# MIC.net
KiCad netlist of a schematic drawn in Altium Designer
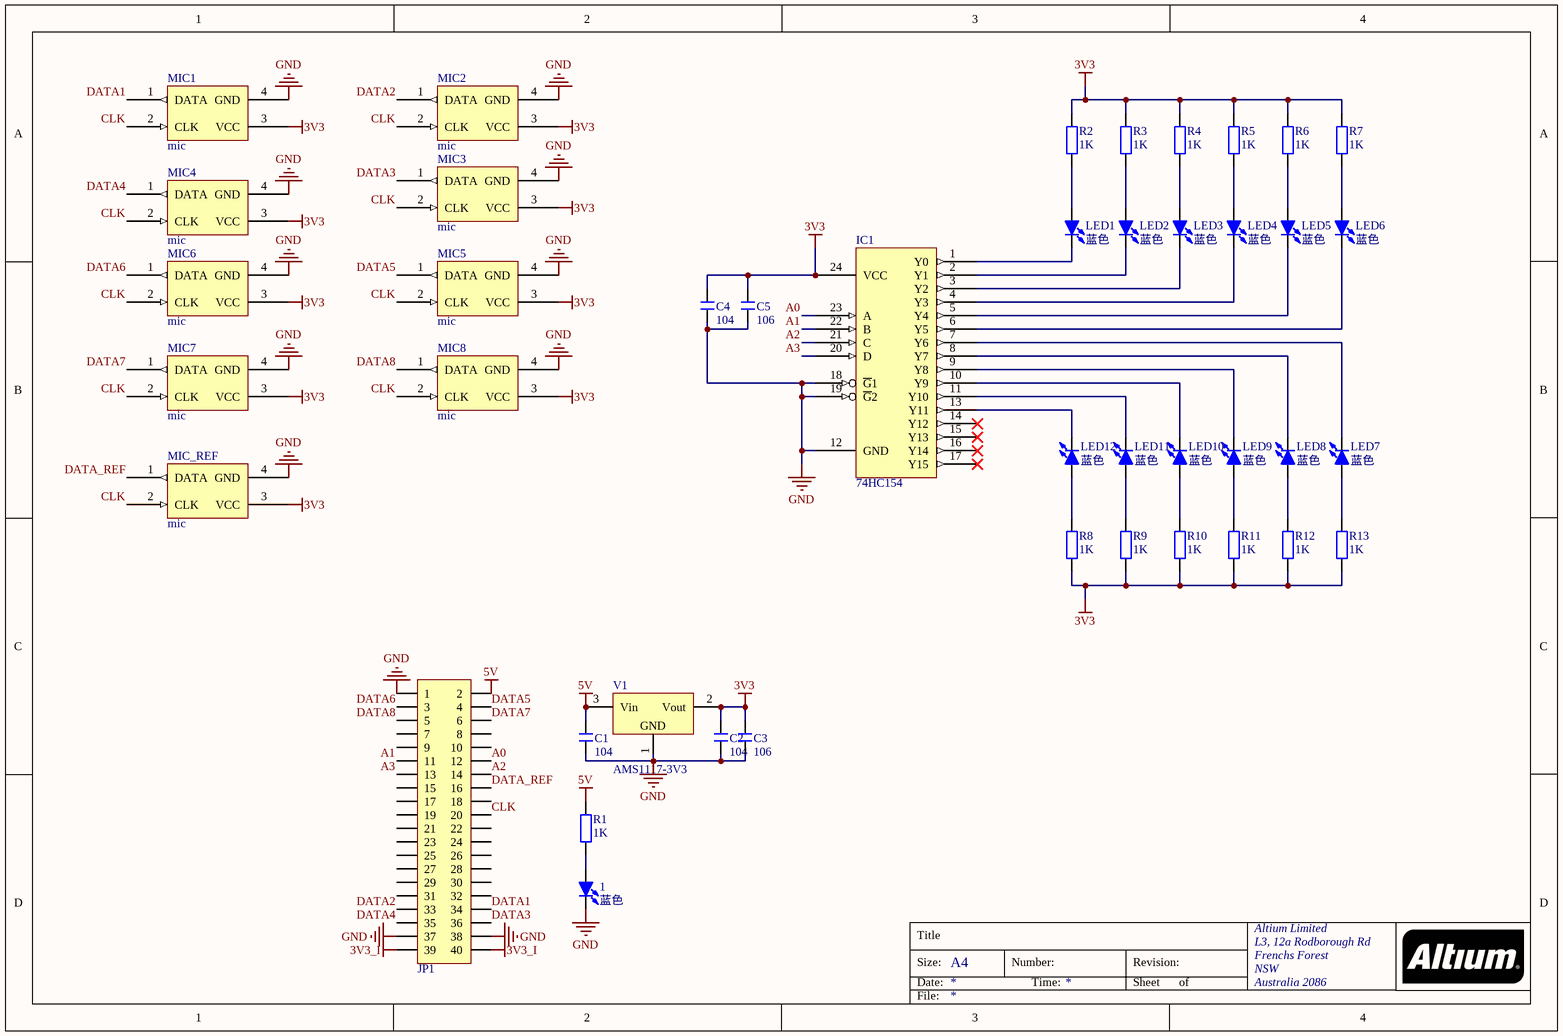
[diagram p0: MIC.SchDoc]

(export (version "E")
  (design (tool "Eeschema 10.0.6"))
  (components
    (comp (ref "1")
      (value "蓝色")
      (footprint "LED 0603B")
      (description "贴片LED")
      (fields (field (name "版权归属") "源创客"))
      (libsource (lib "9.1   - LED") (part "LED-SMD"))
    )
    (comp (ref "C1")
      (value "104")
      (footprint "C 0603_L")
      (description "无极性贴片电容")
      (fields (field (name "版权归属") "源创客"))
      (libsource (lib "3.1   - 电阻-电容-电感") (part "C"))
    )
    (comp (ref "C2")
      (value "104")
      (footprint "C 0603_L")
      (description "无极性贴片电容")
      (fields (field (name "版权归属") "源创客"))
      (libsource (lib "3.1   - 电阻-电容-电感") (part "C"))
    )
    (comp (ref "C3")
      (value "106")
      (footprint "C 0805_M")
      (description "无极性贴片电容")
      (fields (field (name "版权归属") "源创客"))
      (libsource (lib "3.1   - 电阻-电容-电感") (part "C"))
    )
    (comp (ref "C4")
      (value "104")
      (footprint "C 0603_L")
      (description "无极性贴片电容")
      (fields (field (name "版权归属") "源创客"))
      (libsource (lib "3.1   - 电阻-电容-电感") (part "C"))
    )
    (comp (ref "C5")
      (value "106")
      (footprint "C 0805_M")
      (description "无极性贴片电容")
      (fields (field (name "版权归属") "源创客"))
      (libsource (lib "3.1   - 电阻-电容-电感") (part "C"))
    )
    (comp (ref "IC1")
      (value "74HC154")
      (footprint "SOP24_N")
      (description "4线转16线译码器")
      (fields (field (name "版权归属") "源创客"))
      (libsource (lib "1.2   - 74系列芯片") (part "74HC154"))
    )
    (comp (ref "JP1")
      (value "Header 2X11")
      (footprint "HDR2.54-LI-2x20P")
      (description "20*2P接插件")
      (fields (field (name "版权归属") "源创客"))
      (libsource (lib "4.5   - 接插件-脚距2.54") (part "Header 20X2"))
    )
    (comp (ref "LED1")
      (value "蓝色")
      (footprint "LED 0603B")
      (description "贴片LED")
      (fields (field (name "版权归属") "源创客"))
      (libsource (lib "9.1   - LED") (part "LED-SMD"))
    )
    (comp (ref "LED2")
      (value "蓝色")
      (footprint "LED 0603B")
      (description "贴片LED")
      (fields (field (name "版权归属") "源创客"))
      (libsource (lib "9.1   - LED") (part "LED-SMD"))
    )
    (comp (ref "LED3")
      (value "蓝色")
      (footprint "LED 0603B")
      (description "贴片LED")
      (fields (field (name "版权归属") "源创客"))
      (libsource (lib "9.1   - LED") (part "LED-SMD"))
    )
    (comp (ref "LED4")
      (value "蓝色")
      (footprint "LED 0603B")
      (description "贴片LED")
      (fields (field (name "版权归属") "源创客"))
      (libsource (lib "9.1   - LED") (part "LED-SMD"))
    )
    (comp (ref "LED5")
      (value "蓝色")
      (footprint "LED 0603B")
      (description "贴片LED")
      (fields (field (name "版权归属") "源创客"))
      (libsource (lib "9.1   - LED") (part "LED-SMD"))
    )
    (comp (ref "LED6")
      (value "蓝色")
      (footprint "LED 0603B")
      (description "贴片LED")
      (fields (field (name "版权归属") "源创客"))
      (libsource (lib "9.1   - LED") (part "LED-SMD"))
    )
    (comp (ref "LED7")
      (value "蓝色")
      (footprint "LED 0603B")
      (description "贴片LED")
      (fields (field (name "版权归属") "源创客"))
      (libsource (lib "9.1   - LED") (part "LED-SMD"))
    )
    (comp (ref "LED8")
      (value "蓝色")
      (footprint "LED 0603B")
      (description "贴片LED")
      (fields (field (name "版权归属") "源创客"))
      (libsource (lib "9.1   - LED") (part "LED-SMD"))
    )
    (comp (ref "LED9")
      (value "蓝色")
      (footprint "LED 0603B")
      (description "贴片LED")
      (fields (field (name "版权归属") "源创客"))
      (libsource (lib "9.1   - LED") (part "LED-SMD"))
    )
    (comp (ref "LED10")
      (value "蓝色")
      (footprint "LED 0603B")
      (description "贴片LED")
      (fields (field (name "版权归属") "源创客"))
      (libsource (lib "9.1   - LED") (part "LED-SMD"))
    )
    (comp (ref "LED11")
      (value "蓝色")
      (footprint "LED 0603B")
      (description "贴片LED")
      (fields (field (name "版权归属") "源创客"))
      (libsource (lib "9.1   - LED") (part "LED-SMD"))
    )
    (comp (ref "LED12")
      (value "蓝色")
      (footprint "LED 0603B")
      (description "贴片LED")
      (fields (field (name "版权归属") "源创客"))
      (libsource (lib "9.1   - LED") (part "LED-SMD"))
    )
    (comp (ref "MIC1") (value "mic") (footprint "SDM6601") (libsource (lib "MIC") (part "SDM6601P")))
    (comp (ref "MIC2") (value "mic") (footprint "SDM6601") (libsource (lib "MIC") (part "SDM6601P")))
    (comp (ref "MIC3") (value "mic") (footprint "SDM6601") (libsource (lib "MIC") (part "SDM6601P")))
    (comp (ref "MIC4") (value "mic") (footprint "SDM6601") (libsource (lib "MIC") (part "SDM6601P")))
    (comp (ref "MIC5") (value "mic") (footprint "SDM6601") (libsource (lib "MIC") (part "SDM6601P")))
    (comp (ref "MIC6") (value "mic") (footprint "SDM6601") (libsource (lib "MIC") (part "SDM6601P")))
    (comp (ref "MIC7") (value "mic") (footprint "SDM6601") (libsource (lib "MIC") (part "SDM6601P")))
    (comp (ref "MIC8") (value "mic") (footprint "SDM6601") (libsource (lib "MIC") (part "SDM6601P")))
    (comp (ref "MIC_REF") (value "mic") (footprint "SDM6601") (libsource (lib "MIC") (part "SDM6601P")))
    (comp (ref "R1")
      (value "1K")
      (footprint "R 0603_L")
      (description "贴片电阻")
      (fields (field (name "版权归属") "源创客"))
      (libsource (lib "3.1   - 电阻-电容-电感") (part "R"))
    )
    (comp (ref "R2")
      (value "1K")
      (footprint "R 0603_L")
      (description "贴片电阻")
      (fields (field (name "版权归属") "源创客"))
      (libsource (lib "3.1   - 电阻-电容-电感") (part "R"))
    )
    (comp (ref "R3")
      (value "1K")
      (footprint "R 0603_L")
      (description "贴片电阻")
      (fields (field (name "版权归属") "源创客"))
      (libsource (lib "3.1   - 电阻-电容-电感") (part "R"))
    )
    (comp (ref "R4")
      (value "1K")
      (footprint "R 0603_L")
      (description "贴片电阻")
      (fields (field (name "版权归属") "源创客"))
      (libsource (lib "3.1   - 电阻-电容-电感") (part "R"))
    )
    (comp (ref "R5")
      (value "1K")
      (footprint "R 0603_L")
      (description "贴片电阻")
      (fields (field (name "版权归属") "源创客"))
      (libsource (lib "3.1   - 电阻-电容-电感") (part "R"))
    )
    (comp (ref "R6")
      (value "1K")
      (footprint "R 0603_L")
      (description "贴片电阻")
      (fields (field (name "版权归属") "源创客"))
      (libsource (lib "3.1   - 电阻-电容-电感") (part "R"))
    )
    (comp (ref "R7")
      (value "1K")
      (footprint "R 0603_L")
      (description "贴片电阻")
      (fields (field (name "版权归属") "源创客"))
      (libsource (lib "3.1   - 电阻-电容-电感") (part "R"))
    )
    (comp (ref "R8")
      (value "1K")
      (footprint "R 0603_L")
      (description "贴片电阻")
      (fields (field (name "版权归属") "源创客"))
      (libsource (lib "3.1   - 电阻-电容-电感") (part "R"))
    )
    (comp (ref "R9")
      (value "1K")
      (footprint "R 0603_L")
      (description "贴片电阻")
      (fields (field (name "版权归属") "源创客"))
      (libsource (lib "3.1   - 电阻-电容-电感") (part "R"))
    )
    (comp (ref "R10")
      (value "1K")
      (footprint "R 0603_L")
      (description "贴片电阻")
      (fields (field (name "版权归属") "源创客"))
      (libsource (lib "3.1   - 电阻-电容-电感") (part "R"))
    )
    (comp (ref "R11")
      (value "1K")
      (footprint "R 0603_L")
      (description "贴片电阻")
      (fields (field (name "版权归属") "源创客"))
      (libsource (lib "3.1   - 电阻-电容-电感") (part "R"))
    )
    (comp (ref "R12")
      (value "1K")
      (footprint "R 0603_L")
      (description "贴片电阻")
      (fields (field (name "版权归属") "源创客"))
      (libsource (lib "3.1   - 电阻-电容-电感") (part "R"))
    )
    (comp (ref "R13")
      (value "1K")
      (footprint "R 0603_L")
      (description "贴片电阻")
      (fields (field (name "版权归属") "源创客"))
      (libsource (lib "3.1   - 电阻-电容-电感") (part "R"))
    )
    (comp (ref "V1")
      (value "AMS1117-3V3")
      (footprint "SOT223_L")
      (description "三端稳压芯片")
      (fields (field (name "版权归属") "源创客"))
      (libsource (lib "1.3   - 电源类芯片") (part "AMS1117"))
    )
  )
  (nets
    (net (code "1") (name "/A0") (class "Default")
      (node (ref "IC1") (pin "23") (pinfunction "A_23") (pintype "input"))
      (node (ref "JP1") (pin "12") (pinfunction "12_12") (pintype "passive"))
    )
    (net (code "2") (name "/A1") (class "Default")
      (node (ref "IC1") (pin "22") (pinfunction "B_22") (pintype "input"))
      (node (ref "JP1") (pin "11") (pinfunction "11_11") (pintype "passive"))
    )
    (net (code "3") (name "/A2") (class "Default")
      (node (ref "IC1") (pin "21") (pinfunction "C_21") (pintype "input"))
      (node (ref "JP1") (pin "14") (pinfunction "14_14") (pintype "passive"))
    )
    (net (code "4") (name "/A3") (class "Default")
      (node (ref "IC1") (pin "20") (pinfunction "D_20") (pintype "input"))
      (node (ref "JP1") (pin "13") (pinfunction "13_13") (pintype "passive"))
    )
    (net (code "5") (name "/CLK") (class "Default")
      (node (ref "JP1") (pin "20") (pinfunction "20_20") (pintype "passive"))
      (node (ref "MIC1") (pin "2") (pinfunction "CLK_2") (pintype "input"))
      (node (ref "MIC2") (pin "2") (pinfunction "CLK_2") (pintype "input"))
      (node (ref "MIC3") (pin "2") (pinfunction "CLK_2") (pintype "input"))
      (node (ref "MIC4") (pin "2") (pinfunction "CLK_2") (pintype "input"))
      (node (ref "MIC5") (pin "2") (pinfunction "CLK_2") (pintype "input"))
      (node (ref "MIC6") (pin "2") (pinfunction "CLK_2") (pintype "input"))
      (node (ref "MIC7") (pin "2") (pinfunction "CLK_2") (pintype "input"))
      (node (ref "MIC8") (pin "2") (pinfunction "CLK_2") (pintype "input"))
      (node (ref "MIC_REF") (pin "2") (pinfunction "CLK_2") (pintype "input"))
    )
    (net (code "6") (name "/DATA1") (class "Default")
      (node (ref "JP1") (pin "34") (pinfunction "34_34") (pintype "passive"))
      (node (ref "MIC1") (pin "1") (pinfunction "DATA_1") (pintype "output"))
    )
    (net (code "7") (name "/DATA2") (class "Default")
      (node (ref "JP1") (pin "33") (pinfunction "33_33") (pintype "passive"))
      (node (ref "MIC2") (pin "1") (pinfunction "DATA_1") (pintype "output"))
    )
    (net (code "8") (name "/DATA3") (class "Default")
      (node (ref "JP1") (pin "36") (pinfunction "36_36") (pintype "passive"))
      (node (ref "MIC3") (pin "1") (pinfunction "DATA_1") (pintype "output"))
    )
    (net (code "9") (name "/DATA4") (class "Default")
      (node (ref "JP1") (pin "35") (pinfunction "35_35") (pintype "passive"))
      (node (ref "MIC4") (pin "1") (pinfunction "DATA_1") (pintype "output"))
    )
    (net (code "10") (name "/DATA5") (class "Default")
      (node (ref "JP1") (pin "4") (pinfunction "4_4") (pintype "passive"))
      (node (ref "MIC5") (pin "1") (pinfunction "DATA_1") (pintype "output"))
    )
    (net (code "11") (name "/DATA6") (class "Default")
      (node (ref "JP1") (pin "3") (pinfunction "3_3") (pintype "passive"))
      (node (ref "MIC6") (pin "1") (pinfunction "DATA_1") (pintype "output"))
    )
    (net (code "12") (name "/DATA7") (class "Default")
      (node (ref "JP1") (pin "6") (pinfunction "6_6") (pintype "passive"))
      (node (ref "MIC7") (pin "1") (pinfunction "DATA_1") (pintype "output"))
    )
    (net (code "13") (name "/DATA8") (class "Default")
      (node (ref "JP1") (pin "5") (pinfunction "5_5") (pintype "passive"))
      (node (ref "MIC8") (pin "1") (pinfunction "DATA_1") (pintype "output"))
    )
    (net (code "14") (name "/DATA_REF") (class "Default")
      (node (ref "JP1") (pin "16") (pinfunction "16_16") (pintype "passive"))
      (node (ref "MIC_REF") (pin "1") (pinfunction "DATA_1") (pintype "output"))
    )
    (net (code "15") (name "3V3") (class "Default")
      (node (ref "C2") (pin "1") (pinfunction "1_1") (pintype "passive"))
      (node (ref "C3") (pin "1") (pinfunction "1_1") (pintype "passive"))
      (node (ref "C4") (pin "1") (pinfunction "1_1") (pintype "passive"))
      (node (ref "C5") (pin "1") (pinfunction "1_1") (pintype "passive"))
      (node (ref "IC1") (pin "24") (pinfunction "VCC_24") (pintype "power_in"))
      (node (ref "MIC1") (pin "3") (pinfunction "VCC_3") (pintype "power_in"))
      (node (ref "MIC2") (pin "3") (pinfunction "VCC_3") (pintype "power_in"))
      (node (ref "MIC3") (pin "3") (pinfunction "VCC_3") (pintype "power_in"))
      (node (ref "MIC4") (pin "3") (pinfunction "VCC_3") (pintype "power_in"))
      (node (ref "MIC5") (pin "3") (pinfunction "VCC_3") (pintype "power_in"))
      (node (ref "MIC6") (pin "3") (pinfunction "VCC_3") (pintype "power_in"))
      (node (ref "MIC7") (pin "3") (pinfunction "VCC_3") (pintype "power_in"))
      (node (ref "MIC8") (pin "3") (pinfunction "VCC_3") (pintype "power_in"))
      (node (ref "MIC_REF") (pin "3") (pinfunction "VCC_3") (pintype "power_in"))
      (node (ref "R10") (pin "1") (pinfunction "1_1") (pintype "passive"))
      (node (ref "R11") (pin "1") (pinfunction "1_1") (pintype "passive"))
      (node (ref "R12") (pin "1") (pinfunction "1_1") (pintype "passive"))
      (node (ref "R13") (pin "1") (pinfunction "1_1") (pintype "passive"))
      (node (ref "R2") (pin "1") (pinfunction "1_1") (pintype "passive"))
      (node (ref "R3") (pin "1") (pinfunction "1_1") (pintype "passive"))
      (node (ref "R4") (pin "1") (pinfunction "1_1") (pintype "passive"))
      (node (ref "R5") (pin "1") (pinfunction "1_1") (pintype "passive"))
      (node (ref "R6") (pin "1") (pinfunction "1_1") (pintype "passive"))
      (node (ref "R7") (pin "1") (pinfunction "1_1") (pintype "passive"))
      (node (ref "R8") (pin "1") (pinfunction "1_1") (pintype "passive"))
      (node (ref "R9") (pin "1") (pinfunction "1_1") (pintype "passive"))
      (node (ref "V1") (pin "2") (pinfunction "Vout_2") (pintype "passive"))
    )
    (net (code "16") (name "3V3_I") (class "Default")
      (node (ref "JP1") (pin "39") (pinfunction "39_39") (pintype "passive"))
      (node (ref "JP1") (pin "40") (pinfunction "40_40") (pintype "passive"))
    )
    (net (code "17") (name "5V") (class "Default")
      (node (ref "C1") (pin "1") (pinfunction "1_1") (pintype "passive"))
      (node (ref "JP1") (pin "2") (pinfunction "2_2") (pintype "passive"))
      (node (ref "R1") (pin "1") (pinfunction "1_1") (pintype "passive"))
      (node (ref "V1") (pin "3") (pinfunction "Vin_3") (pintype "passive"))
    )
    (net (code "18") (name "GND") (class "Default")
      (node (ref "1") (pin "2") (pinfunction "K_2") (pintype "passive"))
      (node (ref "C1") (pin "2") (pinfunction "2_2") (pintype "passive"))
      (node (ref "C2") (pin "2") (pinfunction "2_2") (pintype "passive"))
      (node (ref "C3") (pin "2") (pinfunction "2_2") (pintype "passive"))
      (node (ref "C4") (pin "2") (pinfunction "2_2") (pintype "passive"))
      (node (ref "C5") (pin "2") (pinfunction "2_2") (pintype "passive"))
      (node (ref "IC1") (pin "12") (pinfunction "GND_12") (pintype "power_in"))
      (node (ref "IC1") (pin "18") (pinfunction "~{G}1_18") (pintype "input"))
      (node (ref "IC1") (pin "19") (pinfunction "~{G}2_19") (pintype "input"))
      (node (ref "JP1") (pin "1") (pinfunction "1_1") (pintype "passive"))
      (node (ref "JP1") (pin "37") (pinfunction "37_37") (pintype "passive"))
      (node (ref "JP1") (pin "38") (pinfunction "38_38") (pintype "passive"))
      (node (ref "MIC1") (pin "4") (pinfunction "GND_4") (pintype "power_in"))
      (node (ref "MIC2") (pin "4") (pinfunction "GND_4") (pintype "power_in"))
      (node (ref "MIC3") (pin "4") (pinfunction "GND_4") (pintype "power_in"))
      (node (ref "MIC4") (pin "4") (pinfunction "GND_4") (pintype "power_in"))
      (node (ref "MIC5") (pin "4") (pinfunction "GND_4") (pintype "power_in"))
      (node (ref "MIC6") (pin "4") (pinfunction "GND_4") (pintype "power_in"))
      (node (ref "MIC7") (pin "4") (pinfunction "GND_4") (pintype "power_in"))
      (node (ref "MIC8") (pin "4") (pinfunction "GND_4") (pintype "power_in"))
      (node (ref "MIC_REF") (pin "4") (pinfunction "GND_4") (pintype "power_in"))
      (node (ref "V1") (pin "1") (pinfunction "GND_1") (pintype "passive"))
    )
    (net (code "19") (name "Net-(1-A)") (class "Default")
      (node (ref "1") (pin "1") (pinfunction "A_1") (pintype "passive"))
      (node (ref "R1") (pin "2") (pinfunction "2_2") (pintype "passive"))
    )
    (net (code "20") (name "Net-(IC1-Y0)") (class "Default")
      (node (ref "IC1") (pin "1") (pinfunction "Y0_1") (pintype "output"))
      (node (ref "LED1") (pin "2") (pinfunction "K_2") (pintype "passive"))
    )
    (net (code "21") (name "Net-(IC1-Y1)") (class "Default")
      (node (ref "IC1") (pin "2") (pinfunction "Y1_2") (pintype "output"))
      (node (ref "LED2") (pin "2") (pinfunction "K_2") (pintype "passive"))
    )
    (net (code "22") (name "Net-(IC1-Y2)") (class "Default")
      (node (ref "IC1") (pin "3") (pinfunction "Y2_3") (pintype "output"))
      (node (ref "LED3") (pin "2") (pinfunction "K_2") (pintype "passive"))
    )
    (net (code "23") (name "Net-(IC1-Y3)") (class "Default")
      (node (ref "IC1") (pin "4") (pinfunction "Y3_4") (pintype "output"))
      (node (ref "LED4") (pin "2") (pinfunction "K_2") (pintype "passive"))
    )
    (net (code "24") (name "Net-(IC1-Y4)") (class "Default")
      (node (ref "IC1") (pin "5") (pinfunction "Y4_5") (pintype "output"))
      (node (ref "LED5") (pin "2") (pinfunction "K_2") (pintype "passive"))
    )
    (net (code "25") (name "Net-(IC1-Y5)") (class "Default")
      (node (ref "IC1") (pin "6") (pinfunction "Y5_6") (pintype "output"))
      (node (ref "LED6") (pin "2") (pinfunction "K_2") (pintype "passive"))
    )
    (net (code "26") (name "Net-(IC1-Y6)") (class "Default")
      (node (ref "IC1") (pin "7") (pinfunction "Y6_7") (pintype "output"))
      (node (ref "LED7") (pin "2") (pinfunction "K_2") (pintype "passive"))
    )
    (net (code "27") (name "Net-(IC1-Y7)") (class "Default")
      (node (ref "IC1") (pin "8") (pinfunction "Y7_8") (pintype "output"))
      (node (ref "LED8") (pin "2") (pinfunction "K_2") (pintype "passive"))
    )
    (net (code "28") (name "Net-(IC1-Y8)") (class "Default")
      (node (ref "IC1") (pin "9") (pinfunction "Y8_9") (pintype "output"))
      (node (ref "LED9") (pin "2") (pinfunction "K_2") (pintype "passive"))
    )
    (net (code "29") (name "Net-(IC1-Y9)") (class "Default")
      (node (ref "IC1") (pin "10") (pinfunction "Y9_10") (pintype "output"))
      (node (ref "LED10") (pin "2") (pinfunction "K_2") (pintype "passive"))
    )
    (net (code "30") (name "Net-(IC1-Y10)") (class "Default")
      (node (ref "IC1") (pin "11") (pinfunction "Y10_11") (pintype "output"))
      (node (ref "LED11") (pin "2") (pinfunction "K_2") (pintype "passive"))
    )
    (net (code "31") (name "Net-(IC1-Y11)") (class "Default")
      (node (ref "IC1") (pin "13") (pinfunction "Y11_13") (pintype "output"))
      (node (ref "LED12") (pin "2") (pinfunction "K_2") (pintype "passive"))
    )
    (net (code "32") (name "Net-(LED1-A)") (class "Default")
      (node (ref "LED1") (pin "1") (pinfunction "A_1") (pintype "passive"))
      (node (ref "R2") (pin "2") (pinfunction "2_2") (pintype "passive"))
    )
    (net (code "33") (name "Net-(LED2-A)") (class "Default")
      (node (ref "LED2") (pin "1") (pinfunction "A_1") (pintype "passive"))
      (node (ref "R3") (pin "2") (pinfunction "2_2") (pintype "passive"))
    )
    (net (code "34") (name "Net-(LED3-A)") (class "Default")
      (node (ref "LED3") (pin "1") (pinfunction "A_1") (pintype "passive"))
      (node (ref "R4") (pin "2") (pinfunction "2_2") (pintype "passive"))
    )
    (net (code "35") (name "Net-(LED4-A)") (class "Default")
      (node (ref "LED4") (pin "1") (pinfunction "A_1") (pintype "passive"))
      (node (ref "R5") (pin "2") (pinfunction "2_2") (pintype "passive"))
    )
    (net (code "36") (name "Net-(LED5-A)") (class "Default")
      (node (ref "LED5") (pin "1") (pinfunction "A_1") (pintype "passive"))
      (node (ref "R6") (pin "2") (pinfunction "2_2") (pintype "passive"))
    )
    (net (code "37") (name "Net-(LED6-A)") (class "Default")
      (node (ref "LED6") (pin "1") (pinfunction "A_1") (pintype "passive"))
      (node (ref "R7") (pin "2") (pinfunction "2_2") (pintype "passive"))
    )
    (net (code "38") (name "Net-(LED7-A)") (class "Default")
      (node (ref "LED7") (pin "1") (pinfunction "A_1") (pintype "passive"))
      (node (ref "R13") (pin "2") (pinfunction "2_2") (pintype "passive"))
    )
    (net (code "39") (name "Net-(LED8-A)") (class "Default")
      (node (ref "LED8") (pin "1") (pinfunction "A_1") (pintype "passive"))
      (node (ref "R12") (pin "2") (pinfunction "2_2") (pintype "passive"))
    )
    (net (code "40") (name "Net-(LED9-A)") (class "Default")
      (node (ref "LED9") (pin "1") (pinfunction "A_1") (pintype "passive"))
      (node (ref "R11") (pin "2") (pinfunction "2_2") (pintype "passive"))
    )
    (net (code "41") (name "Net-(LED10-A)") (class "Default")
      (node (ref "LED10") (pin "1") (pinfunction "A_1") (pintype "passive"))
      (node (ref "R10") (pin "2") (pinfunction "2_2") (pintype "passive"))
    )
    (net (code "42") (name "Net-(LED11-A)") (class "Default")
      (node (ref "LED11") (pin "1") (pinfunction "A_1") (pintype "passive"))
      (node (ref "R9") (pin "2") (pinfunction "2_2") (pintype "passive"))
    )
    (net (code "43") (name "Net-(LED12-A)") (class "Default")
      (node (ref "LED12") (pin "1") (pinfunction "A_1") (pintype "passive"))
      (node (ref "R8") (pin "2") (pinfunction "2_2") (pintype "passive"))
    )
    (net (code "44") (name "unconnected-(IC1-Y12-Pad14)") (class "Default")
      (node (ref "IC1") (pin "14") (pinfunction "Y12_14") (pintype "output+no_connect"))
    )
    (net (code "45") (name "unconnected-(IC1-Y13-Pad15)") (class "Default")
      (node (ref "IC1") (pin "15") (pinfunction "Y13_15") (pintype "output+no_connect"))
    )
    (net (code "46") (name "unconnected-(IC1-Y14-Pad16)") (class "Default")
      (node (ref "IC1") (pin "16") (pinfunction "Y14_16") (pintype "output+no_connect"))
    )
    (net (code "47") (name "unconnected-(IC1-Y15-Pad17)") (class "Default")
      (node (ref "IC1") (pin "17") (pinfunction "Y15_17") (pintype "output+no_connect"))
    )
    (net (code "48") (name "unconnected-(JP1-Pad7)") (class "Default")
      (node (ref "JP1") (pin "7") (pinfunction "7_7") (pintype "passive"))
    )
    (net (code "49") (name "unconnected-(JP1-Pad8)") (class "Default")
      (node (ref "JP1") (pin "8") (pinfunction "8_8") (pintype "passive"))
    )
    (net (code "50") (name "unconnected-(JP1-Pad9)") (class "Default")
      (node (ref "JP1") (pin "9") (pinfunction "9_9") (pintype "passive"))
    )
    (net (code "51") (name "unconnected-(JP1-Pad10)") (class "Default")
      (node (ref "JP1") (pin "10") (pinfunction "10_10") (pintype "passive"))
    )
    (net (code "52") (name "unconnected-(JP1-Pad15)") (class "Default")
      (node (ref "JP1") (pin "15") (pinfunction "15_15") (pintype "passive"))
    )
    (net (code "53") (name "unconnected-(JP1-Pad17)") (class "Default")
      (node (ref "JP1") (pin "17") (pinfunction "17_17") (pintype "passive"))
    )
    (net (code "54") (name "unconnected-(JP1-Pad18)") (class "Default")
      (node (ref "JP1") (pin "18") (pinfunction "18_18") (pintype "passive"))
    )
    (net (code "55") (name "unconnected-(JP1-Pad19)") (class "Default")
      (node (ref "JP1") (pin "19") (pinfunction "19_19") (pintype "passive"))
    )
    (net (code "56") (name "unconnected-(JP1-Pad21)") (class "Default")
      (node (ref "JP1") (pin "21") (pinfunction "21_21") (pintype "passive"))
    )
    (net (code "57") (name "unconnected-(JP1-Pad22)") (class "Default")
      (node (ref "JP1") (pin "22") (pinfunction "22_22") (pintype "passive"))
    )
    (net (code "58") (name "unconnected-(JP1-Pad23)") (class "Default")
      (node (ref "JP1") (pin "23") (pinfunction "23_23") (pintype "passive"))
    )
    (net (code "59") (name "unconnected-(JP1-Pad24)") (class "Default")
      (node (ref "JP1") (pin "24") (pinfunction "24_24") (pintype "passive"))
    )
    (net (code "60") (name "unconnected-(JP1-Pad25)") (class "Default")
      (node (ref "JP1") (pin "25") (pinfunction "25_25") (pintype "passive"))
    )
    (net (code "61") (name "unconnected-(JP1-Pad26)") (class "Default")
      (node (ref "JP1") (pin "26") (pinfunction "26_26") (pintype "passive"))
    )
    (net (code "62") (name "unconnected-(JP1-Pad27)") (class "Default")
      (node (ref "JP1") (pin "27") (pinfunction "27_27") (pintype "passive"))
    )
    (net (code "63") (name "unconnected-(JP1-Pad28)") (class "Default")
      (node (ref "JP1") (pin "28") (pinfunction "28_28") (pintype "passive"))
    )
    (net (code "64") (name "unconnected-(JP1-Pad29)") (class "Default")
      (node (ref "JP1") (pin "29") (pinfunction "29_29") (pintype "passive"))
    )
    (net (code "65") (name "unconnected-(JP1-Pad30)") (class "Default")
      (node (ref "JP1") (pin "30") (pinfunction "30_30") (pintype "passive"))
    )
    (net (code "66") (name "unconnected-(JP1-Pad31)") (class "Default")
      (node (ref "JP1") (pin "31") (pinfunction "31_31") (pintype "passive"))
    )
    (net (code "67") (name "unconnected-(JP1-Pad32)") (class "Default")
      (node (ref "JP1") (pin "32") (pinfunction "32_32") (pintype "passive"))
    )
  )
)
